# Z7_ETHERNET.net
KiCad netlist of a schematic drawn in Altium Designer
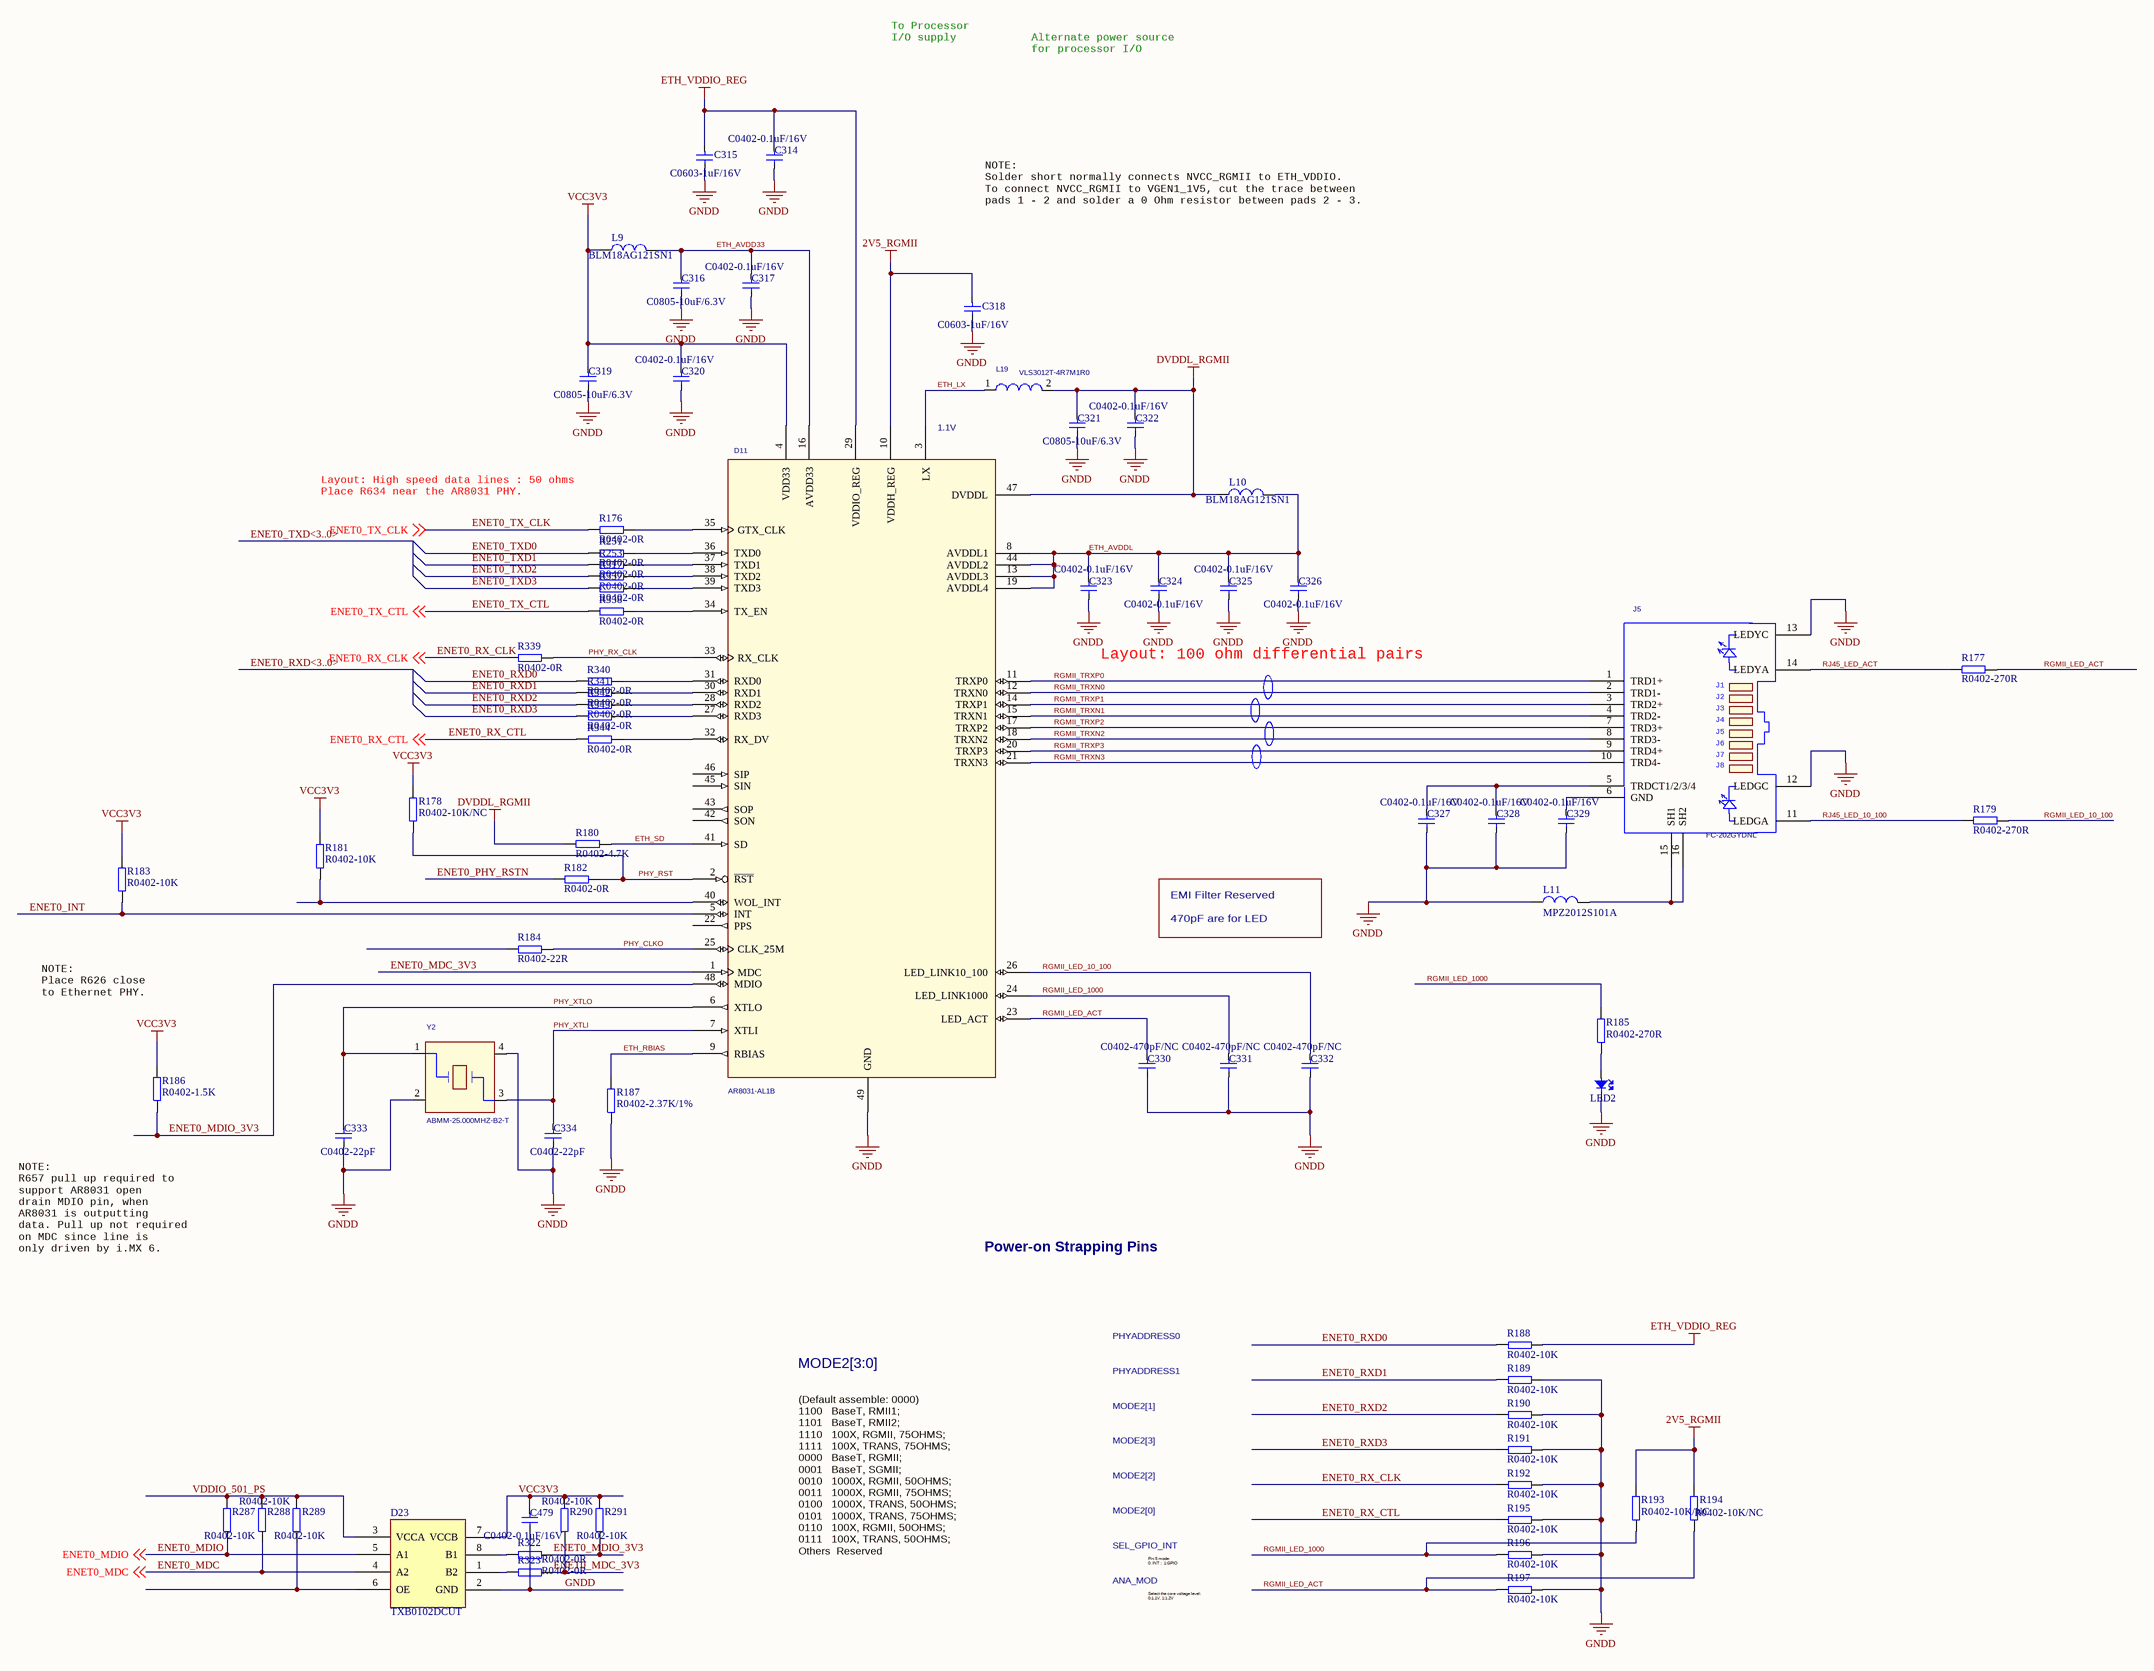
[diagram p0: Z7_ETHERNET.SchDoc]

(export (version "E")
  (design (tool "Eeschema 10.0.6"))
  (components
    (comp (ref "C314")
      (value "C0402-0.1uF/16V")
      (footprint "C0402")
      (description "X7R")
      (fields (field (name "SCHEMATIC_PART") "CAP") (field (name "MANUFACTURER") "SAMSUNG"))
      (libsource (lib "Database_Libs1") (part "CAP"))
    )
    (comp (ref "C315")
      (value "C0603-1uF/16V")
      (footprint "C0603")
      (description "X7R")
      (fields (field (name "SCHEMATIC_PART") "CAP"))
      (libsource (lib "Database_Libs1") (part "CAP"))
    )
    (comp (ref "C316")
      (value "C0805-10uF/6.3V")
      (footprint "C0805")
      (fields (field (name "SCHEMATIC_PART") "CAP"))
      (libsource (lib "Database_Libs1") (part "CAP"))
    )
    (comp (ref "C317")
      (value "C0402-0.1uF/16V")
      (footprint "C0402")
      (description "X7R")
      (fields (field (name "SCHEMATIC_PART") "CAP") (field (name "MANUFACTURER") "SAMSUNG"))
      (libsource (lib "Database_Libs1") (part "CAP"))
    )
    (comp (ref "C318")
      (value "C0603-1uF/16V")
      (footprint "C0603")
      (description "X7R")
      (fields (field (name "SCHEMATIC_PART") "CAP"))
      (libsource (lib "Database_Libs1") (part "CAP"))
    )
    (comp (ref "C319")
      (value "C0805-10uF/6.3V")
      (footprint "C0805")
      (fields (field (name "SCHEMATIC_PART") "CAP"))
      (libsource (lib "Database_Libs1") (part "CAP"))
    )
    (comp (ref "C320")
      (value "C0402-0.1uF/16V")
      (footprint "C0402")
      (description "X7R")
      (fields (field (name "SCHEMATIC_PART") "CAP") (field (name "MANUFACTURER") "SAMSUNG"))
      (libsource (lib "Database_Libs1") (part "CAP"))
    )
    (comp (ref "C321")
      (value "C0805-10uF/6.3V")
      (footprint "C0805")
      (fields (field (name "SCHEMATIC_PART") "CAP"))
      (libsource (lib "Database_Libs1") (part "CAP"))
    )
    (comp (ref "C322")
      (value "C0402-0.1uF/16V")
      (footprint "C0402")
      (description "X7R")
      (fields (field (name "SCHEMATIC_PART") "CAP") (field (name "MANUFACTURER") "SAMSUNG"))
      (libsource (lib "Database_Libs1") (part "CAP"))
    )
    (comp (ref "C323")
      (value "C0402-0.1uF/16V")
      (footprint "C0402")
      (description "X7R")
      (fields (field (name "SCHEMATIC_PART") "CAP") (field (name "MANUFACTURER") "SAMSUNG"))
      (libsource (lib "Database_Libs1") (part "CAP"))
    )
    (comp (ref "C324")
      (value "C0402-0.1uF/16V")
      (footprint "C0402")
      (description "X7R")
      (fields (field (name "SCHEMATIC_PART") "CAP") (field (name "MANUFACTURER") "SAMSUNG"))
      (libsource (lib "Database_Libs1") (part "CAP"))
    )
    (comp (ref "C325")
      (value "C0402-0.1uF/16V")
      (footprint "C0402")
      (description "X7R")
      (fields (field (name "SCHEMATIC_PART") "CAP") (field (name "MANUFACTURER") "SAMSUNG"))
      (libsource (lib "Database_Libs1") (part "CAP"))
    )
    (comp (ref "C326")
      (value "C0402-0.1uF/16V")
      (footprint "C0402")
      (description "X7R")
      (fields (field (name "SCHEMATIC_PART") "CAP") (field (name "MANUFACTURER") "SAMSUNG"))
      (libsource (lib "Database_Libs1") (part "CAP"))
    )
    (comp (ref "C327")
      (value "C0402-0.1uF/16V")
      (footprint "C0402")
      (description "X7R")
      (fields (field (name "SCHEMATIC_PART") "CAP") (field (name "MANUFACTURER") "SAMSUNG"))
      (libsource (lib "Database_Libs1") (part "CAP"))
    )
    (comp (ref "C328")
      (value "C0402-0.1uF/16V")
      (footprint "C0402")
      (description "X7R")
      (fields (field (name "SCHEMATIC_PART") "CAP") (field (name "MANUFACTURER") "SAMSUNG"))
      (libsource (lib "Database_Libs1") (part "CAP"))
    )
    (comp (ref "C329")
      (value "C0402-0.1uF/16V")
      (footprint "C0402")
      (description "X7R")
      (fields (field (name "SCHEMATIC_PART") "CAP") (field (name "MANUFACTURER") "SAMSUNG"))
      (libsource (lib "Database_Libs1") (part "CAP"))
    )
    (comp (ref "C330")
      (value "C0402-470pF/NC")
      (footprint "C0402")
      (description "X7R")
      (fields (field (name "SCHEMATIC_PART") "CAP") (field (name "MANUFACTURER") "SAMSUNG"))
      (libsource (lib "Database_Libs1") (part "CAP"))
    )
    (comp (ref "C331")
      (value "C0402-470pF/NC")
      (footprint "C0402")
      (description "X7R")
      (fields (field (name "SCHEMATIC_PART") "CAP") (field (name "MANUFACTURER") "SAMSUNG"))
      (libsource (lib "Database_Libs1") (part "CAP"))
    )
    (comp (ref "C332")
      (value "C0402-470pF/NC")
      (footprint "C0402")
      (description "X7R")
      (fields (field (name "SCHEMATIC_PART") "CAP") (field (name "MANUFACTURER") "SAMSUNG"))
      (libsource (lib "Database_Libs1") (part "CAP"))
    )
    (comp (ref "C333")
      (value "C0402-22pF")
      (footprint "C0402")
      (description "X7R")
      (fields (field (name "SCHEMATIC_PART") "CAP") (field (name "MANUFACTURER") "SAMSUNG"))
      (libsource (lib "Database_Libs1") (part "CAP"))
    )
    (comp (ref "C334")
      (value "C0402-22pF")
      (footprint "C0402")
      (description "X7R")
      (fields (field (name "SCHEMATIC_PART") "CAP") (field (name "MANUFACTURER") "SAMSUNG"))
      (libsource (lib "Database_Libs1") (part "CAP"))
    )
    (comp (ref "C479")
      (value "C0402-0.1uF/16V")
      (footprint "C0402")
      (description "X7R")
      (fields (field (name "SCHEMATIC_PART") "CAP") (field (name "MANUFACTURER") "SAMSUNG"))
      (libsource (lib "Database_Libs1") (part "CAP"))
    )
    (comp (ref "D11")
      (value "AR8031-AL1B")
      (description "IC XCVR ETHERNET PHY 10/100/1000G-BIT 3.3V QFN48")
      (libsource (lib "*") (part "AR8031_QFN48"))
    )
    (comp (ref "D23") (value "TXB0102DCUT") (footprint "MSOP-8") (libsource (lib "SCHLIB1") (part "TXB0102")))
    (comp (ref "J5")
      (value "FC-202GYDNL")
      (description "CON 10 RJ-45 SHLD TH G/Y LEDS 50MIL SP 662H AU 125L")
      (libsource (lib "*") (part "V890-1AX1-A1_2"))
    )
    (comp (ref "L9")
      (value "BLM18AG121SN1")
      (footprint "R0603")
      (fields (field (name "SCHEMATIC_PART") "BEAD") (field (name "MANUFACTURER") "村田"))
      (libsource (lib "Database_Libs1") (part "BEAD"))
    )
    (comp (ref "L10")
      (value "BLM18AG121SN1")
      (footprint "R0603")
      (fields (field (name "SCHEMATIC_PART") "BEAD") (field (name "MANUFACTURER") "村田"))
      (libsource (lib "Database_Libs1") (part "BEAD"))
    )
    (comp (ref "L11")
      (value "MPZ2012S101A")
      (footprint "R0805")
      (fields (field (name "SCHEMATIC_PART") "BEAD") (field (name "MANUFACTURER") "TDK"))
      (libsource (lib "Database_Libs1") (part "BEAD"))
    )
    (comp (ref "L19")
      (value "VLS3012T-4R7M1R0")
      (description "IND PWR 4.7UH@1MHZ 1A 20% SMD")
      (fields (field (name "TOLERANCE") "20%"))
      (libsource (lib "*") (part "INDUCTOR_0"))
    )
    (comp (ref "LED2")
      (value "LED0603-GREEN")
      (footprint "LED-R0603")
      (description "表贴发光二极管, 0603封装, 体积1.6x0.8mm, 绿色, 高度0.8mm")
      (libsource (lib "*") (part "LED-R_3"))
    )
    (comp (ref "R176")
      (value "R0402-0R")
      (footprint "R0402")
      (fields (field (name "SCHEMATIC_PART") "RES") (field (name "MANUFACTURER") "SAMSUNG"))
      (libsource (lib "Database_Libs1") (part "RES"))
    )
    (comp (ref "R177")
      (value "R0402-270R")
      (footprint "R0402")
      (fields (field (name "SCHEMATIC_PART") "RES") (field (name "MANUFACTURER") "SAMSUNG"))
      (libsource (lib "Database_Libs1") (part "RES"))
    )
    (comp (ref "R178")
      (value "R0402-10K/NC")
      (footprint "R0402")
      (fields (field (name "SCHEMATIC_PART") "RES") (field (name "MANUFACTURER") "SAMSUNG"))
      (libsource (lib "Database_Libs1") (part "RES"))
    )
    (comp (ref "R179")
      (value "R0402-270R")
      (footprint "R0402")
      (fields (field (name "SCHEMATIC_PART") "RES") (field (name "MANUFACTURER") "SAMSUNG"))
      (libsource (lib "Database_Libs1") (part "RES"))
    )
    (comp (ref "R180")
      (value "R0402-4.7K")
      (footprint "R0402")
      (fields (field (name "SCHEMATIC_PART") "RES") (field (name "MANUFACTURER") "SAMSUNG"))
      (libsource (lib "Database_Libs1") (part "RES"))
    )
    (comp (ref "R181")
      (value "R0402-10K")
      (footprint "R0402")
      (fields (field (name "SCHEMATIC_PART") "RES") (field (name "MANUFACTURER") "SAMSUNG"))
      (libsource (lib "Database_Libs1") (part "RES"))
    )
    (comp (ref "R182")
      (value "R0402-0R")
      (footprint "R0402")
      (fields (field (name "SCHEMATIC_PART") "RES") (field (name "MANUFACTURER") "SAMSUNG"))
      (libsource (lib "Database_Libs1") (part "RES"))
    )
    (comp (ref "R183")
      (value "R0402-10K")
      (footprint "R0402")
      (fields (field (name "SCHEMATIC_PART") "RES") (field (name "MANUFACTURER") "SAMSUNG"))
      (libsource (lib "Database_Libs1") (part "RES"))
    )
    (comp (ref "R184")
      (value "R0402-22R")
      (footprint "R0402")
      (fields (field (name "SCHEMATIC_PART") "RES") (field (name "MANUFACTURER") "SAMSUNG"))
      (libsource (lib "Database_Libs1") (part "RES"))
    )
    (comp (ref "R185")
      (value "R0402-270R")
      (footprint "R0402")
      (fields (field (name "SCHEMATIC_PART") "RES") (field (name "MANUFACTURER") "SAMSUNG"))
      (libsource (lib "Database_Libs1") (part "RES"))
    )
    (comp (ref "R186")
      (value "R0402-1.5K")
      (footprint "R0402")
      (fields (field (name "SCHEMATIC_PART") "RES") (field (name "MANUFACTURER") "SAMSUNG"))
      (libsource (lib "Database_Libs1") (part "RES"))
    )
    (comp (ref "R187")
      (value "R0402-2.37K/1%")
      (footprint "R0402")
      (fields (field (name "SCHEMATIC_PART") "RES") (field (name "MANUFACTURER") "SAMSUNG"))
      (libsource (lib "Database_Libs1") (part "RES"))
    )
    (comp (ref "R188")
      (value "R0402-10K")
      (footprint "R0402")
      (fields (field (name "SCHEMATIC_PART") "RES") (field (name "MANUFACTURER") "SAMSUNG"))
      (libsource (lib "Database_Libs1") (part "RES"))
    )
    (comp (ref "R189")
      (value "R0402-10K")
      (footprint "R0402")
      (fields (field (name "SCHEMATIC_PART") "RES") (field (name "MANUFACTURER") "SAMSUNG"))
      (libsource (lib "Database_Libs1") (part "RES"))
    )
    (comp (ref "R190")
      (value "R0402-10K")
      (footprint "R0402")
      (fields (field (name "SCHEMATIC_PART") "RES") (field (name "MANUFACTURER") "SAMSUNG"))
      (libsource (lib "Database_Libs1") (part "RES"))
    )
    (comp (ref "R191")
      (value "R0402-10K")
      (footprint "R0402")
      (fields (field (name "SCHEMATIC_PART") "RES") (field (name "MANUFACTURER") "SAMSUNG"))
      (libsource (lib "Database_Libs1") (part "RES"))
    )
    (comp (ref "R192")
      (value "R0402-10K")
      (footprint "R0402")
      (fields (field (name "SCHEMATIC_PART") "RES") (field (name "MANUFACTURER") "SAMSUNG"))
      (libsource (lib "Database_Libs1") (part "RES"))
    )
    (comp (ref "R193")
      (value "R0402-10K/NC")
      (footprint "R0402")
      (fields (field (name "SCHEMATIC_PART") "RES") (field (name "MANUFACTURER") "SAMSUNG"))
      (libsource (lib "Database_Libs1") (part "RES"))
    )
    (comp (ref "R194")
      (value "R0402-10K/NC")
      (footprint "R0402")
      (fields (field (name "SCHEMATIC_PART") "RES") (field (name "MANUFACTURER") "SAMSUNG"))
      (libsource (lib "Database_Libs1") (part "RES"))
    )
    (comp (ref "R195")
      (value "R0402-10K")
      (footprint "R0402")
      (fields (field (name "SCHEMATIC_PART") "RES") (field (name "MANUFACTURER") "SAMSUNG"))
      (libsource (lib "Database_Libs1") (part "RES"))
    )
    (comp (ref "R196")
      (value "R0402-10K")
      (footprint "R0402")
      (fields (field (name "SCHEMATIC_PART") "RES") (field (name "MANUFACTURER") "SAMSUNG"))
      (libsource (lib "Database_Libs1") (part "RES"))
    )
    (comp (ref "R197")
      (value "R0402-10K")
      (footprint "R0402")
      (fields (field (name "SCHEMATIC_PART") "RES") (field (name "MANUFACTURER") "SAMSUNG"))
      (libsource (lib "Database_Libs1") (part "RES"))
    )
    (comp (ref "R251")
      (value "R0402-0R")
      (footprint "R0402")
      (fields (field (name "SCHEMATIC_PART") "RES") (field (name "MANUFACTURER") "SAMSUNG"))
      (libsource (lib "Database_Libs1") (part "RES"))
    )
    (comp (ref "R253")
      (value "R0402-0R")
      (footprint "R0402")
      (fields (field (name "SCHEMATIC_PART") "RES") (field (name "MANUFACTURER") "SAMSUNG"))
      (libsource (lib "Database_Libs1") (part "RES"))
    )
    (comp (ref "R287")
      (value "R0402-10K")
      (footprint "R0402")
      (fields (field (name "SCHEMATIC_PART") "RES") (field (name "MANUFACTURER") "SAMSUNG"))
      (libsource (lib "Database_Libs1") (part "RES"))
    )
    (comp (ref "R288")
      (value "R0402-10K")
      (footprint "R0402")
      (fields (field (name "SCHEMATIC_PART") "RES") (field (name "MANUFACTURER") "SAMSUNG"))
      (libsource (lib "Database_Libs1") (part "RES"))
    )
    (comp (ref "R289")
      (value "R0402-10K")
      (footprint "R0402")
      (fields (field (name "SCHEMATIC_PART") "RES") (field (name "MANUFACTURER") "SAMSUNG"))
      (libsource (lib "Database_Libs1") (part "RES"))
    )
    (comp (ref "R290")
      (value "R0402-10K")
      (footprint "R0402")
      (fields (field (name "SCHEMATIC_PART") "RES") (field (name "MANUFACTURER") "SAMSUNG"))
      (libsource (lib "Database_Libs1") (part "RES"))
    )
    (comp (ref "R291")
      (value "R0402-10K")
      (footprint "R0402")
      (fields (field (name "SCHEMATIC_PART") "RES") (field (name "MANUFACTURER") "SAMSUNG"))
      (libsource (lib "Database_Libs1") (part "RES"))
    )
    (comp (ref "R317")
      (value "R0402-0R")
      (footprint "R0402")
      (fields (field (name "SCHEMATIC_PART") "RES") (field (name "MANUFACTURER") "SAMSUNG"))
      (libsource (lib "Database_Libs1") (part "RES"))
    )
    (comp (ref "R322")
      (value "R0402-0R")
      (footprint "R0402")
      (fields (field (name "SCHEMATIC_PART") "RES") (field (name "MANUFACTURER") "SAMSUNG"))
      (libsource (lib "Database_Libs1") (part "RES"))
    )
    (comp (ref "R323")
      (value "R0402-0R")
      (footprint "R0402")
      (fields (field (name "SCHEMATIC_PART") "RES") (field (name "MANUFACTURER") "SAMSUNG"))
      (libsource (lib "Database_Libs1") (part "RES"))
    )
    (comp (ref "R337")
      (value "R0402-0R")
      (footprint "R0402")
      (fields (field (name "SCHEMATIC_PART") "RES") (field (name "MANUFACTURER") "SAMSUNG"))
      (libsource (lib "Database_Libs1") (part "RES"))
    )
    (comp (ref "R338")
      (value "R0402-0R")
      (footprint "R0402")
      (fields (field (name "SCHEMATIC_PART") "RES") (field (name "MANUFACTURER") "SAMSUNG"))
      (libsource (lib "Database_Libs1") (part "RES"))
    )
    (comp (ref "R339")
      (value "R0402-0R")
      (footprint "R0402")
      (fields (field (name "SCHEMATIC_PART") "RES") (field (name "MANUFACTURER") "SAMSUNG"))
      (libsource (lib "Database_Libs1") (part "RES"))
    )
    (comp (ref "R340")
      (value "R0402-0R")
      (footprint "R0402")
      (fields (field (name "SCHEMATIC_PART") "RES") (field (name "MANUFACTURER") "SAMSUNG"))
      (libsource (lib "Database_Libs1") (part "RES"))
    )
    (comp (ref "R341")
      (value "R0402-0R")
      (footprint "R0402")
      (fields (field (name "SCHEMATIC_PART") "RES") (field (name "MANUFACTURER") "SAMSUNG"))
      (libsource (lib "Database_Libs1") (part "RES"))
    )
    (comp (ref "R342")
      (value "R0402-0R")
      (footprint "R0402")
      (fields (field (name "SCHEMATIC_PART") "RES") (field (name "MANUFACTURER") "SAMSUNG"))
      (libsource (lib "Database_Libs1") (part "RES"))
    )
    (comp (ref "R343")
      (value "R0402-0R")
      (footprint "R0402")
      (fields (field (name "SCHEMATIC_PART") "RES") (field (name "MANUFACTURER") "SAMSUNG"))
      (libsource (lib "Database_Libs1") (part "RES"))
    )
    (comp (ref "R344")
      (value "R0402-0R")
      (footprint "R0402")
      (fields (field (name "SCHEMATIC_PART") "RES") (field (name "MANUFACTURER") "SAMSUNG"))
      (libsource (lib "Database_Libs1") (part "RES"))
    )
    (comp (ref "Y2")
      (value "ABMM-25.000MHZ-B2-T")
      (description "XTAL 25MHZ -- -- SMT")
      (libsource (lib "*") (part "XTAL_13Y"))
    )
  )
  (nets
    (net (code "3") (name "/ENET0_INT") (class "Default")
      (node (ref "D11") (pin "5") (pinfunction "INT_5") (pintype "bidirectional"))
      (node (ref "R183") (pin "1") (pintype "passive"))
    )
    (net (code "4") (name "/ENET0_MDC_3V3") (class "Default")
      (node (ref "D11") (pin "1") (pinfunction "MDC_1") (pintype "input"))
      (node (ref "R290") (pin "1") (pintype "passive"))
      (node (ref "R323") (pin "2") (pintype "passive"))
    )
    (net (code "5") (name "/ENET0_MDIO_3V3") (class "Default")
      (node (ref "D11") (pin "48") (pinfunction "MDIO_48") (pintype "bidirectional"))
      (node (ref "R186") (pin "1") (pintype "passive"))
      (node (ref "R291") (pin "1") (pintype "passive"))
      (node (ref "R322") (pin "2") (pintype "passive"))
    )
    (net (code "6") (name "/ENET0_PHY_RSTN") (class "Default")
      (node (ref "R182") (pin "1") (pintype "passive"))
    )
    (net (code "7") (name "/ENET0_RXD0") (class "Default")
      (node (ref "R188") (pin "1") (pintype "passive"))
      (node (ref "R340") (pin "1") (pintype "passive"))
    )
    (net (code "8") (name "/ENET0_RXD1") (class "Default")
      (node (ref "R189") (pin "1") (pintype "passive"))
      (node (ref "R341") (pin "1") (pintype "passive"))
    )
    (net (code "9") (name "/ENET0_RXD2") (class "Default")
      (node (ref "R190") (pin "1") (pintype "passive"))
      (node (ref "R342") (pin "1") (pintype "passive"))
    )
    (net (code "10") (name "/ENET0_RXD3") (class "Default")
      (node (ref "R191") (pin "1") (pintype "passive"))
      (node (ref "R343") (pin "1") (pintype "passive"))
    )
    (net (code "11") (name "/ENET0_TXD0") (class "Default") (node (ref "R251") (pin "1") (pintype "passive")))
    (net (code "12") (name "/ENET0_TXD1") (class "Default") (node (ref "R253") (pin "1") (pintype "passive")))
    (net (code "13") (name "/ENET0_TXD2") (class "Default") (node (ref "R317") (pin "1") (pintype "passive")))
    (net (code "14") (name "/ENET0_TXD3") (class "Default") (node (ref "R337") (pin "1") (pintype "passive")))
    (net (code "15") (name "/ETH_AVDD33") (class "Default")
      (node (ref "C316") (pin "1") (pinfunction "1_1") (pintype "passive"))
      (node (ref "C317") (pin "1") (pinfunction "1_1") (pintype "passive"))
      (node (ref "D11") (pin "16") (pinfunction "AVDD33_16") (pintype "power_in"))
      (node (ref "L9") (pin "2") (pinfunction "2_2") (pintype "passive"))
    )
    (net (code "16") (name "/ETH_AVDDL") (class "Default")
      (node (ref "C323") (pin "1") (pinfunction "1_1") (pintype "passive"))
      (node (ref "C324") (pin "1") (pinfunction "1_1") (pintype "passive"))
      (node (ref "C325") (pin "1") (pinfunction "1_1") (pintype "passive"))
      (node (ref "C326") (pin "1") (pinfunction "1_1") (pintype "passive"))
      (node (ref "D11") (pin "13") (pinfunction "AVDDL3_13") (pintype "power_in"))
      (node (ref "D11") (pin "19") (pinfunction "AVDDL4_19") (pintype "power_in"))
      (node (ref "D11") (pin "44") (pinfunction "AVDDL2_44") (pintype "power_in"))
      (node (ref "D11") (pin "8") (pinfunction "AVDDL1_8") (pintype "power_in"))
      (node (ref "L10") (pin "2") (pinfunction "2_2") (pintype "passive"))
    )
    (net (code "17") (name "/ETH_LX") (class "Default")
      (node (ref "D11") (pin "3") (pinfunction "LX_3") (pintype "power_in"))
      (node (ref "L19") (pin "1") (pinfunction "1_1") (pintype "passive"))
    )
    (net (code "18") (name "/ETH_RBIAS") (class "Default")
      (node (ref "D11") (pin "9") (pinfunction "RBIAS_9") (pintype "output"))
      (node (ref "R187") (pin "2") (pintype "passive"))
    )
    (net (code "19") (name "/ETH_SD") (class "Default")
      (node (ref "D11") (pin "41") (pinfunction "SD_41") (pintype "input"))
      (node (ref "R180") (pin "1") (pintype "passive"))
    )
    (net (code "20") (name "/PHY_CLKO") (class "Default")
      (node (ref "D11") (pin "25") (pinfunction "CLK_25M_25") (pintype "bidirectional"))
      (node (ref "R184") (pin "2") (pintype "passive"))
    )
    (net (code "21") (name "/PHY_RST") (class "Default")
      (node (ref "D11") (pin "2") (pinfunction "~{RST}_2") (pintype "input"))
      (node (ref "R178") (pin "1") (pintype "passive"))
      (node (ref "R182") (pin "2") (pintype "passive"))
    )
    (net (code "22") (name "/PHY_RX_CLK") (class "Default")
      (node (ref "D11") (pin "33") (pinfunction "RX_CLK_33") (pintype "bidirectional"))
      (node (ref "R339") (pin "2") (pintype "passive"))
    )
    (net (code "23") (name "/PHY_XTLI") (class "Default")
      (node (ref "C334") (pin "1") (pinfunction "1_1") (pintype "passive"))
      (node (ref "D11") (pin "7") (pinfunction "XTLI_7") (pintype "input"))
      (node (ref "Y2") (pin "3") (pinfunction "3_3") (pintype "passive"))
    )
    (net (code "24") (name "/PHY_XTLO") (class "Default")
      (node (ref "C333") (pin "1") (pinfunction "1_1") (pintype "passive"))
      (node (ref "D11") (pin "6") (pinfunction "XTLO_6") (pintype "output"))
      (node (ref "Y2") (pin "1") (pinfunction "1_1") (pintype "passive"))
    )
    (net (code "25") (name "/RGMII_LED_10_100") (class "Default")
      (node (ref "C332") (pin "1") (pinfunction "1_1") (pintype "passive"))
      (node (ref "D11") (pin "26") (pinfunction "LED_LINK10_100_26") (pintype "bidirectional"))
      (node (ref "R179") (pin "1") (pintype "passive"))
    )
    (net (code "26") (name "/RGMII_LED_1000") (class "Default")
      (node (ref "C331") (pin "1") (pinfunction "1_1") (pintype "passive"))
      (node (ref "D11") (pin "24") (pinfunction "LED_LINK1000_24") (pintype "bidirectional"))
      (node (ref "R185") (pin "2") (pintype "passive"))
      (node (ref "R193") (pin "1") (pintype "passive"))
      (node (ref "R196") (pin "1") (pintype "passive"))
    )
    (net (code "27") (name "/RGMII_LED_ACT") (class "Default")
      (node (ref "C330") (pin "1") (pinfunction "1_1") (pintype "passive"))
      (node (ref "D11") (pin "23") (pinfunction "LED_ACT_23") (pintype "bidirectional"))
      (node (ref "R177") (pin "1") (pintype "passive"))
      (node (ref "R194") (pin "1") (pintype "passive"))
      (node (ref "R197") (pin "1") (pintype "passive"))
    )
    (net (code "28") (name "/RGMII_TRXN0") (class "Default")
      (node (ref "D11") (pin "12") (pinfunction "TRXN0_12") (pintype "bidirectional"))
      (node (ref "J5") (pin "2") (pinfunction "TRD1-_2") (pintype "passive"))
    )
    (net (code "29") (name "/RGMII_TRXN1") (class "Default")
      (node (ref "D11") (pin "15") (pinfunction "TRXN1_15") (pintype "bidirectional"))
      (node (ref "J5") (pin "4") (pinfunction "TRD2-_4") (pintype "passive"))
    )
    (net (code "30") (name "/RGMII_TRXN2") (class "Default")
      (node (ref "D11") (pin "18") (pinfunction "TRXN2_18") (pintype "bidirectional"))
      (node (ref "J5") (pin "8") (pinfunction "TRD3-_8") (pintype "passive"))
    )
    (net (code "31") (name "/RGMII_TRXN3") (class "Default")
      (node (ref "D11") (pin "21") (pinfunction "TRXN3_21") (pintype "bidirectional"))
      (node (ref "J5") (pin "10") (pinfunction "TRD4-_10") (pintype "passive"))
    )
    (net (code "32") (name "/RGMII_TRXP0") (class "Default")
      (node (ref "D11") (pin "11") (pinfunction "TRXP0_11") (pintype "bidirectional"))
      (node (ref "J5") (pin "1") (pinfunction "TRD1+_1") (pintype "passive"))
    )
    (net (code "33") (name "/RGMII_TRXP1") (class "Default")
      (node (ref "D11") (pin "14") (pinfunction "TRXP1_14") (pintype "bidirectional"))
      (node (ref "J5") (pin "3") (pinfunction "TRD2+_3") (pintype "passive"))
    )
    (net (code "34") (name "/RGMII_TRXP2") (class "Default")
      (node (ref "D11") (pin "17") (pinfunction "TRXP2_17") (pintype "bidirectional"))
      (node (ref "J5") (pin "7") (pinfunction "TRD3+_7") (pintype "passive"))
    )
    (net (code "35") (name "/RGMII_TRXP3") (class "Default")
      (node (ref "D11") (pin "20") (pinfunction "TRXP3_20") (pintype "bidirectional"))
      (node (ref "J5") (pin "9") (pinfunction "TRD4+_9") (pintype "passive"))
    )
    (net (code "36") (name "/RJ45_LED_10_100") (class "Default")
      (node (ref "J5") (pin "11") (pinfunction "LEDGA_11") (pintype "passive"))
      (node (ref "R179") (pin "2") (pintype "passive"))
    )
    (net (code "37") (name "/RJ45_LED_ACT") (class "Default")
      (node (ref "J5") (pin "14") (pinfunction "LEDYA_14") (pintype "passive"))
      (node (ref "R177") (pin "2") (pintype "passive"))
    )
    (net (code "38") (name "/VDDIO_501_PS") (class "Default")
      (node (ref "D23") (pin "3") (pinfunction "VCCA_3") (pintype "passive"))
      (node (ref "R287") (pin "2") (pintype "passive"))
      (node (ref "R288") (pin "2") (pintype "passive"))
      (node (ref "R289") (pin "2") (pintype "passive"))
    )
    (net (code "41") (name "2V5_RGMII") (class "Default")
      (node (ref "C318") (pin "1") (pinfunction "1_1") (pintype "passive"))
      (node (ref "D11") (pin "10") (pinfunction "VDDH_REG_10") (pintype "power_in"))
      (node (ref "R193") (pin "2") (pintype "passive"))
      (node (ref "R194") (pin "2") (pintype "passive"))
    )
    (net (code "42") (name "DVDDL_RGMII") (class "Default")
      (node (ref "C321") (pin "1") (pinfunction "1_1") (pintype "passive"))
      (node (ref "C322") (pin "1") (pinfunction "1_1") (pintype "passive"))
      (node (ref "D11") (pin "47") (pinfunction "DVDDL_47") (pintype "power_in"))
      (node (ref "L10") (pin "1") (pinfunction "1_1") (pintype "passive"))
      (node (ref "L19") (pin "2") (pinfunction "2_2") (pintype "passive"))
      (node (ref "R180") (pin "2") (pintype "passive"))
    )
    (net (code "43") (name "ENET0_MDC") (class "Default")
      (node (ref "D23") (pin "4") (pinfunction "A2_4") (pintype "passive"))
      (node (ref "R288") (pin "1") (pintype "passive"))
    )
    (net (code "44") (name "ENET0_MDIO") (class "Default")
      (node (ref "D23") (pin "5") (pinfunction "A1_5") (pintype "passive"))
      (node (ref "R287") (pin "1") (pintype "passive"))
    )
    (net (code "45") (name "ENET0_RX_CLK") (class "Default")
      (node (ref "R192") (pin "1") (pintype "passive"))
      (node (ref "R339") (pin "1") (pintype "passive"))
    )
    (net (code "46") (name "ENET0_RX_CTL") (class "Default")
      (node (ref "R195") (pin "1") (pintype "passive"))
      (node (ref "R344") (pin "1") (pintype "passive"))
    )
    (net (code "47") (name "ENET0_TX_CLK") (class "Default")
      (node (ref "R176") (pin "1") (pintype "passive"))
    )
    (net (code "48") (name "ENET0_TX_CTL") (class "Default")
      (node (ref "R338") (pin "1") (pintype "passive"))
    )
    (net (code "49") (name "ETH_VDDIO_REG") (class "Default")
      (node (ref "C314") (pin "1") (pinfunction "1_1") (pintype "passive"))
      (node (ref "C315") (pin "1") (pinfunction "1_1") (pintype "passive"))
      (node (ref "D11") (pin "29") (pinfunction "VDDIO_REG_29") (pintype "power_in"))
      (node (ref "R188") (pin "2") (pintype "passive"))
    )
    (net (code "50") (name "GNDD") (class "Default")
      (node (ref "C314") (pin "2") (pinfunction "2_2") (pintype "passive"))
      (node (ref "C315") (pin "2") (pinfunction "2_2") (pintype "passive"))
      (node (ref "C316") (pin "2") (pinfunction "2_2") (pintype "passive"))
      (node (ref "C317") (pin "2") (pinfunction "2_2") (pintype "passive"))
      (node (ref "C318") (pin "2") (pinfunction "2_2") (pintype "passive"))
      (node (ref "C319") (pin "2") (pinfunction "2_2") (pintype "passive"))
      (node (ref "C320") (pin "2") (pinfunction "2_2") (pintype "passive"))
      (node (ref "C321") (pin "2") (pinfunction "2_2") (pintype "passive"))
      (node (ref "C322") (pin "2") (pinfunction "2_2") (pintype "passive"))
      (node (ref "C323") (pin "2") (pinfunction "2_2") (pintype "passive"))
      (node (ref "C324") (pin "2") (pinfunction "2_2") (pintype "passive"))
      (node (ref "C325") (pin "2") (pinfunction "2_2") (pintype "passive"))
      (node (ref "C326") (pin "2") (pinfunction "2_2") (pintype "passive"))
      (node (ref "C327") (pin "2") (pinfunction "2_2") (pintype "passive"))
      (node (ref "C328") (pin "2") (pinfunction "2_2") (pintype "passive"))
      (node (ref "C329") (pin "2") (pinfunction "2_2") (pintype "passive"))
      (node (ref "C330") (pin "2") (pinfunction "2_2") (pintype "passive"))
      (node (ref "C331") (pin "2") (pinfunction "2_2") (pintype "passive"))
      (node (ref "C332") (pin "2") (pinfunction "2_2") (pintype "passive"))
      (node (ref "C333") (pin "2") (pinfunction "2_2") (pintype "passive"))
      (node (ref "C334") (pin "2") (pinfunction "2_2") (pintype "passive"))
      (node (ref "C479") (pin "2") (pinfunction "2_2") (pintype "passive"))
      (node (ref "D11") (pin "49") (pinfunction "GND_49") (pintype "power_in"))
      (node (ref "D23") (pin "2") (pinfunction "GND_2") (pintype "passive"))
      (node (ref "J5") (pin "12") (pinfunction "LEDGC_12") (pintype "passive"))
      (node (ref "J5") (pin "13") (pinfunction "LEDYC_13") (pintype "passive"))
      (node (ref "L11") (pin "1") (pinfunction "1_1") (pintype "passive"))
      (node (ref "LED2") (pin "2") (pinfunction "K_2") (pintype "passive"))
      (node (ref "R187") (pin "1") (pintype "passive"))
      (node (ref "R189") (pin "2") (pintype "passive"))
      (node (ref "R190") (pin "2") (pintype "passive"))
      (node (ref "R191") (pin "2") (pintype "passive"))
      (node (ref "R192") (pin "2") (pintype "passive"))
      (node (ref "R195") (pin "2") (pintype "passive"))
      (node (ref "R196") (pin "2") (pintype "passive"))
      (node (ref "R197") (pin "2") (pintype "passive"))
      (node (ref "Y2") (pin "2") (pinfunction "2_2") (pintype "power_in"))
      (node (ref "Y2") (pin "4") (pinfunction "4_4") (pintype "power_in"))
    )
    (net (code "51") (name "Net-(D11-GTX_CLK)") (class "Default")
      (node (ref "D11") (pin "35") (pinfunction "GTX_CLK_35") (pintype "input"))
      (node (ref "R176") (pin "2") (pintype "passive"))
    )
    (net (code "52") (name "Net-(D11-RXD0)") (class "Default")
      (node (ref "D11") (pin "31") (pinfunction "RXD0_31") (pintype "bidirectional"))
      (node (ref "R340") (pin "2") (pintype "passive"))
    )
    (net (code "53") (name "Net-(D11-RXD1)") (class "Default")
      (node (ref "D11") (pin "30") (pinfunction "RXD1_30") (pintype "bidirectional"))
      (node (ref "R341") (pin "2") (pintype "passive"))
    )
    (net (code "54") (name "Net-(D11-RXD2)") (class "Default")
      (node (ref "D11") (pin "28") (pinfunction "RXD2_28") (pintype "bidirectional"))
      (node (ref "R342") (pin "2") (pintype "passive"))
    )
    (net (code "55") (name "Net-(D11-RXD3)") (class "Default")
      (node (ref "D11") (pin "27") (pinfunction "RXD3_27") (pintype "bidirectional"))
      (node (ref "R343") (pin "2") (pintype "passive"))
    )
    (net (code "56") (name "Net-(D11-RX_DV)") (class "Default")
      (node (ref "D11") (pin "32") (pinfunction "RX_DV_32") (pintype "bidirectional"))
      (node (ref "R344") (pin "2") (pintype "passive"))
    )
    (net (code "57") (name "Net-(D11-TXD0)") (class "Default")
      (node (ref "D11") (pin "36") (pinfunction "TXD0_36") (pintype "input"))
      (node (ref "R251") (pin "2") (pintype "passive"))
    )
    (net (code "58") (name "Net-(D11-TXD1)") (class "Default")
      (node (ref "D11") (pin "37") (pinfunction "TXD1_37") (pintype "input"))
      (node (ref "R253") (pin "2") (pintype "passive"))
    )
    (net (code "59") (name "Net-(D11-TXD2)") (class "Default")
      (node (ref "D11") (pin "38") (pinfunction "TXD2_38") (pintype "input"))
      (node (ref "R317") (pin "2") (pintype "passive"))
    )
    (net (code "60") (name "Net-(D11-TXD3)") (class "Default")
      (node (ref "D11") (pin "39") (pinfunction "TXD3_39") (pintype "input"))
      (node (ref "R337") (pin "2") (pintype "passive"))
    )
    (net (code "61") (name "Net-(D11-TX_EN)") (class "Default")
      (node (ref "D11") (pin "34") (pinfunction "TX_EN_34") (pintype "input"))
      (node (ref "R338") (pin "2") (pintype "passive"))
    )
    (net (code "62") (name "Net-(D11-WOL_INT)") (class "Default")
      (node (ref "D11") (pin "40") (pinfunction "WOL_INT_40") (pintype "bidirectional"))
      (node (ref "R181") (pin "1") (pintype "passive"))
    )
    (net (code "63") (name "Net-(D23-B1)") (class "Default")
      (node (ref "D23") (pin "8") (pinfunction "B1_8") (pintype "passive"))
      (node (ref "R322") (pin "1") (pintype "passive"))
    )
    (net (code "64") (name "Net-(D23-B2)") (class "Default")
      (node (ref "D23") (pin "1") (pinfunction "B2_1") (pintype "passive"))
      (node (ref "R323") (pin "1") (pintype "passive"))
    )
    (net (code "65") (name "Net-(D23-OE)") (class "Default")
      (node (ref "D23") (pin "6") (pinfunction "OE_6") (pintype "passive"))
      (node (ref "R289") (pin "1") (pintype "passive"))
    )
    (net (code "66") (name "Net-(J5-GND)") (class "Default")
      (node (ref "C329") (pin "1") (pinfunction "1_1") (pintype "passive"))
      (node (ref "J5") (pin "6") (pinfunction "GND_6") (pintype "power_in"))
    )
    (net (code "67") (name "Net-(J5-SH1)") (class "Default")
      (node (ref "J5") (pin "15") (pinfunction "SH1_15") (pintype "passive"))
      (node (ref "J5") (pin "16") (pinfunction "SH2_16") (pintype "passive"))
      (node (ref "L11") (pin "2") (pinfunction "2_2") (pintype "passive"))
    )
    (net (code "68") (name "Net-(J5-TRDCT1{slash}2{slash}3{slash}4)") (class "Default")
      (node (ref "C327") (pin "1") (pinfunction "1_1") (pintype "passive"))
      (node (ref "C328") (pin "1") (pinfunction "1_1") (pintype "passive"))
      (node (ref "J5") (pin "5") (pinfunction "TRDCT1/2/3/4_5") (pintype "passive"))
    )
    (net (code "69") (name "Net-(LED2-A)") (class "Default")
      (node (ref "LED2") (pin "1") (pinfunction "A_1") (pintype "passive"))
      (node (ref "R185") (pin "1") (pintype "passive"))
    )
    (net (code "70") (name "VCC3V3") (class "Default")
      (node (ref "C319") (pin "1") (pinfunction "1_1") (pintype "passive"))
      (node (ref "C320") (pin "1") (pinfunction "1_1") (pintype "passive"))
      (node (ref "C479") (pin "1") (pinfunction "1_1") (pintype "passive"))
      (node (ref "D11") (pin "4") (pinfunction "VDD33_4") (pintype "power_in"))
      (node (ref "D23") (pin "7") (pinfunction "VCCB_7") (pintype "passive"))
      (node (ref "L9") (pin "1") (pinfunction "1_1") (pintype "passive"))
      (node (ref "R178") (pin "2") (pintype "passive"))
      (node (ref "R181") (pin "2") (pintype "passive"))
      (node (ref "R183") (pin "2") (pintype "passive"))
      (node (ref "R186") (pin "2") (pintype "passive"))
      (node (ref "R290") (pin "2") (pintype "passive"))
      (node (ref "R291") (pin "2") (pintype "passive"))
    )
    (net (code "71") (name "unconnected-(D11-PPS-Pad22)") (class "Default")
      (node (ref "D11") (pin "22") (pinfunction "PPS_22") (pintype "output"))
    )
    (net (code "72") (name "unconnected-(D11-SIN-Pad45)") (class "Default")
      (node (ref "D11") (pin "45") (pinfunction "SIN_45") (pintype "input"))
    )
    (net (code "73") (name "unconnected-(D11-SIP-Pad46)") (class "Default")
      (node (ref "D11") (pin "46") (pinfunction "SIP_46") (pintype "input"))
    )
    (net (code "74") (name "unconnected-(D11-SON-Pad42)") (class "Default")
      (node (ref "D11") (pin "42") (pinfunction "SON_42") (pintype "output"))
    )
    (net (code "75") (name "unconnected-(D11-SOP-Pad43)") (class "Default")
      (node (ref "D11") (pin "43") (pinfunction "SOP_43") (pintype "output"))
    )
    (net (code "76") (name "unconnected-(R184-Pad1)") (class "Default")
      (node (ref "R184") (pin "1") (pintype "passive"))
    )
  )
)
